# simple-loop2.net
KiCad netlist of a schematic drawn in EAGLE
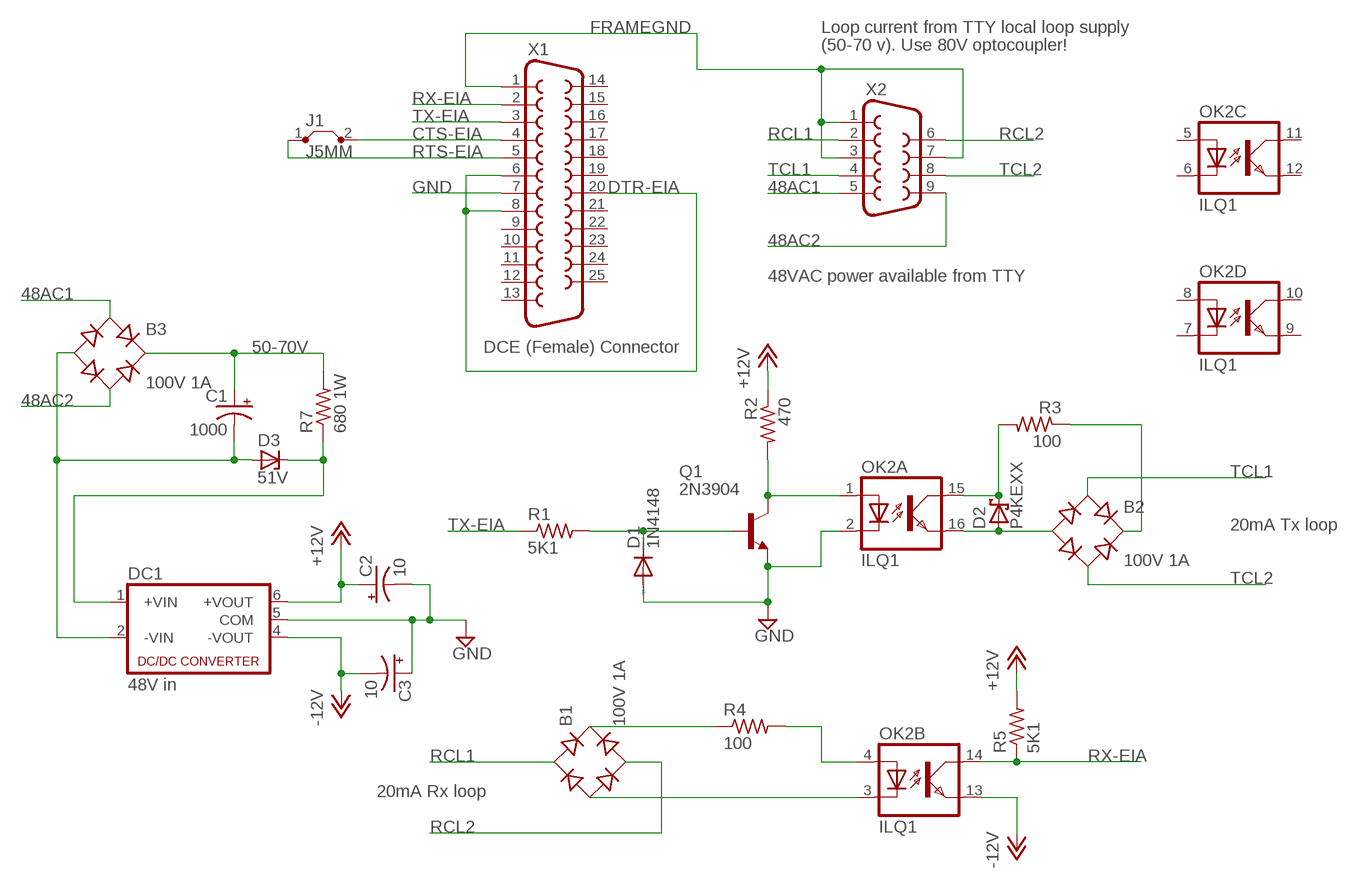
[diagram p0: schematic, sheet 1]

(export (version "E")
  (design (tool "Eeschema 10.0.6"))
  (components
    (comp (ref "B1")
      (value "100V 1A")
      (footprint "eagle-import:RB1A")
      (libsource (lib "eagle-import") (part "RB1A"))
    )
    (comp (ref "B2")
      (value "100V 1A")
      (footprint "eagle-import:RB1A")
      (libsource (lib "eagle-import") (part "RB1A"))
    )
    (comp (ref "B3")
      (value "100V 1A")
      (footprint "eagle-import:RB1A")
      (libsource (lib "eagle-import") (part "RB1A"))
    )
    (comp (ref "C1")
      (value "1000")
      (footprint "eagle-import:E7,5-18")
      (libsource (lib "eagle-import") (part "CPOL-USE7.5-18"))
    )
    (comp (ref "C2")
      (value "10")
      (footprint "eagle-import:B45181A")
      (libsource (lib "eagle-import") (part "CPOL-USB45181A"))
    )
    (comp (ref "C3")
      (value "10")
      (footprint "eagle-import:B45181A")
      (libsource (lib "eagle-import") (part "CPOL-USB45181A"))
    )
    (comp (ref "D1")
      (value "1N4148")
      (footprint "eagle-import:DO35-10")
      (libsource (lib "eagle-import") (part "1N4148DO35-10"))
    )
    (comp (ref "D2")
      (value "P4KEXX")
      (footprint "eagle-import:DO41-10")
      (libsource (lib "eagle-import") (part "P4KEXX"))
    )
    (comp (ref "D3")
      (value "51V")
      (footprint "eagle-import:DO41Z10")
      (libsource (lib "eagle-import") (part "ZENER-DIODEDO41Z10"))
    )
    (comp (ref "DC1")
      (value "48V in")
      (footprint "eagle-import:NMA")
      (fields (field (name "MF") "C & D TECHNOLOGIES, INC") (field (name "MPN") "NMA0515SC"))
      (libsource (lib "eagle-import") (part "NMA"))
    )
    (comp (ref "J1")
      (value "J5MM")
      (footprint "eagle-import:05")
      (libsource (lib "eagle-import") (part "J5MM"))
    )
    (comp (ref "OK2")
      (value "ILQ1")
      (footprint "eagle-import:DIL16")
      (fields (field (name "MF") "VISHAY/TELEFUNKEN"))
      (libsource (lib "eagle-import") (part "ILQ1"))
    )
    (comp (ref "Q1")
      (value "2N3904")
      (footprint "eagle-import:TO92")
      (libsource (lib "eagle-import") (part "2N3904"))
    )
    (comp (ref "R1")
      (value "5K1")
      (footprint "eagle-import:0207_10")
      (libsource (lib "eagle-import") (part "R-US_0207/10"))
    )
    (comp (ref "R2")
      (value "470")
      (footprint "eagle-import:0207_10")
      (libsource (lib "eagle-import") (part "R-US_0207/10"))
    )
    (comp (ref "R3")
      (value "100")
      (footprint "eagle-import:0207_10")
      (libsource (lib "eagle-import") (part "R-US_0207/10"))
    )
    (comp (ref "R4")
      (value "100")
      (footprint "eagle-import:0207_10")
      (libsource (lib "eagle-import") (part "R-US_0207/10"))
    )
    (comp (ref "R5")
      (value "5K1")
      (footprint "eagle-import:0207_10")
      (libsource (lib "eagle-import") (part "R-US_0207/10"))
    )
    (comp (ref "R7")
      (value "680 1W")
      (footprint "eagle-import:0617_17")
      (libsource (lib "eagle-import") (part "R-US_0617/17"))
    )
    (comp (ref "X1")
      (value "F25H")
      (footprint "eagle-import:F25H")
      (libsource (lib "eagle-import") (part "F25H"))
    )
    (comp (ref "X2")
      (value "F09H")
      (footprint "eagle-import:F09H")
      (libsource (lib "eagle-import") (part "F09H"))
    )
  )
  (nets
    (net (code "1") (name "+12V") (class "Default")
      (node (ref "C2") (pin "+") (pinfunction "+_+") (pintype "passive"))
      (node (ref "DC1") (pin "6") (pinfunction "+VOUT_6") (pintype "passive"))
      (node (ref "R2") (pin "1") (pinfunction "1_1") (pintype "passive"))
      (node (ref "R5") (pin "2") (pinfunction "2_2") (pintype "passive"))
    )
    (net (code "2") (name "-12V") (class "Default")
      (node (ref "C3") (pin "-") (pinfunction "-_-") (pintype "passive"))
      (node (ref "DC1") (pin "4") (pinfunction "-VOUT_4") (pintype "passive"))
      (node (ref "OK2") (pin "13") (pinfunction "EMIT_13") (pintype "passive"))
    )
    (net (code "3") (name "/48AC1") (class "Default")
      (node (ref "B3") (pin "AC1") (pinfunction "AC1_AC1") (pintype "passive"))
      (node (ref "X2") (pin "5") (pinfunction "5_5") (pintype "passive"))
    )
    (net (code "4") (name "/48AC2") (class "Default")
      (node (ref "B3") (pin "AC2") (pinfunction "AC2_AC2") (pintype "passive"))
      (node (ref "X2") (pin "9") (pinfunction "9_9") (pintype "passive"))
    )
    (net (code "5") (name "/50-70V") (class "Default")
      (node (ref "B3") (pin "+") (pinfunction "+_+") (pintype "passive"))
      (node (ref "C1") (pin "+") (pinfunction "+_+") (pintype "passive"))
      (node (ref "R7") (pin "2") (pinfunction "2_2") (pintype "passive"))
    )
    (net (code "6") (name "/CTS-EIA") (class "Default")
      (node (ref "J1") (pin "2") (pinfunction "2_2") (pintype "passive"))
      (node (ref "X1") (pin "4") (pinfunction "4_4") (pintype "passive"))
    )
    (net (code "7") (name "/DTR-EIA") (class "Default")
      (node (ref "X1") (pin "20") (pinfunction "20_20") (pintype "passive"))
      (node (ref "X1") (pin "6") (pinfunction "6_6") (pintype "passive"))
      (node (ref "X1") (pin "8") (pinfunction "8_8") (pintype "passive"))
    )
    (net (code "8") (name "/FRAMEGND") (class "Default")
      (node (ref "X1") (pin "1") (pinfunction "1_1") (pintype "passive"))
      (node (ref "X2") (pin "1") (pinfunction "1_1") (pintype "passive"))
      (node (ref "X2") (pin "3") (pinfunction "3_3") (pintype "passive"))
      (node (ref "X2") (pin "7") (pinfunction "7_7") (pintype "passive"))
    )
    (net (code "9") (name "/RCL1") (class "Default")
      (node (ref "B1") (pin "AC1") (pinfunction "AC1_AC1") (pintype "passive"))
      (node (ref "X2") (pin "2") (pinfunction "2_2") (pintype "passive"))
    )
    (net (code "10") (name "/RCL2") (class "Default")
      (node (ref "B1") (pin "AC2") (pinfunction "AC2_AC2") (pintype "passive"))
      (node (ref "X2") (pin "6") (pinfunction "6_6") (pintype "passive"))
    )
    (net (code "11") (name "/RTS-EIA") (class "Default")
      (node (ref "J1") (pin "1") (pinfunction "1_1") (pintype "passive"))
      (node (ref "X1") (pin "5") (pinfunction "5_5") (pintype "passive"))
    )
    (net (code "12") (name "/RX-EIA") (class "Default")
      (node (ref "OK2") (pin "14") (pinfunction "COL_14") (pintype "passive"))
      (node (ref "R5") (pin "1") (pinfunction "1_1") (pintype "passive"))
      (node (ref "X1") (pin "2") (pinfunction "2_2") (pintype "passive"))
    )
    (net (code "13") (name "/TCL1") (class "Default")
      (node (ref "B2") (pin "AC1") (pinfunction "AC1_AC1") (pintype "passive"))
      (node (ref "X2") (pin "4") (pinfunction "4_4") (pintype "passive"))
    )
    (net (code "14") (name "/TCL2") (class "Default")
      (node (ref "B2") (pin "AC2") (pinfunction "AC2_AC2") (pintype "passive"))
      (node (ref "X2") (pin "8") (pinfunction "8_8") (pintype "passive"))
    )
    (net (code "15") (name "/TX-EIA") (class "Default")
      (node (ref "R1") (pin "1") (pinfunction "1_1") (pintype "passive"))
      (node (ref "X1") (pin "3") (pinfunction "3_3") (pintype "passive"))
    )
    (net (code "16") (name "GND") (class "Default")
      (node (ref "C2") (pin "-") (pinfunction "-_-") (pintype "passive"))
      (node (ref "C3") (pin "+") (pinfunction "+_+") (pintype "passive"))
      (node (ref "D1") (pin "A") (pinfunction "A_A") (pintype "passive"))
      (node (ref "DC1") (pin "5") (pinfunction "COM_5") (pintype "passive"))
      (node (ref "OK2") (pin "2") (pinfunction "C_2") (pintype "passive"))
      (node (ref "Q1") (pin "3") (pinfunction "E_3") (pintype "passive"))
      (node (ref "X1") (pin "7") (pinfunction "7_7") (pintype "passive"))
    )
    (net (code "17") (name "Net-(B1-Pad+)") (class "Default")
      (node (ref "B1") (pin "+") (pinfunction "+_+") (pintype "passive"))
      (node (ref "R4") (pin "1") (pinfunction "1_1") (pintype "passive"))
    )
    (net (code "18") (name "Net-(B2-Pad+)") (class "Default")
      (node (ref "B2") (pin "+") (pinfunction "+_+") (pintype "passive"))
      (node (ref "R3") (pin "1") (pinfunction "1_1") (pintype "passive"))
    )
    (net (code "19") (name "Net-(DC1-+VIN)") (class "Default")
      (node (ref "D3") (pin "C") (pinfunction "C_C") (pintype "passive"))
      (node (ref "DC1") (pin "1") (pinfunction "+VIN_1") (pintype "passive"))
      (node (ref "R7") (pin "1") (pinfunction "1_1") (pintype "passive"))
    )
    (net (code "20") (name "Net-(DC1--VIN)") (class "Default")
      (node (ref "B3") (pin "-") (pinfunction "-_-") (pintype "passive"))
      (node (ref "C1") (pin "-") (pinfunction "-_-") (pintype "passive"))
      (node (ref "D3") (pin "A") (pinfunction "A_A") (pintype "passive"))
      (node (ref "DC1") (pin "2") (pinfunction "-VIN_2") (pintype "passive"))
    )
    (net (code "21") (name "Net-(OK2A-A)") (class "Default")
      (node (ref "OK2") (pin "1") (pinfunction "A_1") (pintype "passive"))
      (node (ref "Q1") (pin "1") (pinfunction "C_1") (pintype "passive"))
      (node (ref "R2") (pin "2") (pinfunction "2_2") (pintype "passive"))
    )
    (net (code "22") (name "Net-(OK2A-COL)") (class "Default")
      (node (ref "D2") (pin "C") (pinfunction "C_C") (pintype "passive"))
      (node (ref "OK2") (pin "15") (pinfunction "COL_15") (pintype "passive"))
      (node (ref "R3") (pin "2") (pinfunction "2_2") (pintype "passive"))
    )
    (net (code "23") (name "Net-(OK2A-EMIT)") (class "Default")
      (node (ref "B2") (pin "-") (pinfunction "-_-") (pintype "passive"))
      (node (ref "D2") (pin "A") (pinfunction "A_A") (pintype "passive"))
      (node (ref "OK2") (pin "16") (pinfunction "EMIT_16") (pintype "passive"))
    )
    (net (code "24") (name "Net-(OK2B-A)") (class "Default")
      (node (ref "OK2") (pin "4") (pinfunction "A_4") (pintype "passive"))
      (node (ref "R4") (pin "2") (pinfunction "2_2") (pintype "passive"))
    )
    (net (code "25") (name "Net-(OK2B-C)") (class "Default")
      (node (ref "B1") (pin "-") (pinfunction "-_-") (pintype "passive"))
      (node (ref "OK2") (pin "3") (pinfunction "C_3") (pintype "passive"))
    )
    (net (code "26") (name "Net-(Q1-B)") (class "Default")
      (node (ref "D1") (pin "C") (pinfunction "C_C") (pintype "passive"))
      (node (ref "Q1") (pin "2") (pinfunction "B_2") (pintype "passive"))
      (node (ref "R1") (pin "2") (pinfunction "2_2") (pintype "passive"))
    )
    (net (code "27") (name "unconnected-(OK2C-A-Pad5)") (class "Default")
      (node (ref "OK2") (pin "5") (pinfunction "A_5") (pintype "passive"))
    )
    (net (code "28") (name "unconnected-(OK2C-C-Pad6)") (class "Default")
      (node (ref "OK2") (pin "6") (pinfunction "C_6") (pintype "passive"))
    )
    (net (code "29") (name "unconnected-(OK2C-COL-Pad11)") (class "Default")
      (node (ref "OK2") (pin "11") (pinfunction "COL_11") (pintype "passive"))
    )
    (net (code "30") (name "unconnected-(OK2C-EMIT-Pad12)") (class "Default")
      (node (ref "OK2") (pin "12") (pinfunction "EMIT_12") (pintype "passive"))
    )
    (net (code "31") (name "unconnected-(OK2D-A-Pad8)") (class "Default")
      (node (ref "OK2") (pin "8") (pinfunction "A_8") (pintype "passive"))
    )
    (net (code "32") (name "unconnected-(OK2D-C-Pad7)") (class "Default")
      (node (ref "OK2") (pin "7") (pinfunction "C_7") (pintype "passive"))
    )
    (net (code "33") (name "unconnected-(OK2D-COL-Pad10)") (class "Default")
      (node (ref "OK2") (pin "10") (pinfunction "COL_10") (pintype "passive"))
    )
    (net (code "34") (name "unconnected-(OK2D-EMIT-Pad9)") (class "Default")
      (node (ref "OK2") (pin "9") (pinfunction "EMIT_9") (pintype "passive"))
    )
    (net (code "35") (name "unconnected-(X1-Pad9)") (class "Default")
      (node (ref "X1") (pin "9") (pinfunction "9_9") (pintype "passive"))
    )
    (net (code "36") (name "unconnected-(X1-Pad10)") (class "Default")
      (node (ref "X1") (pin "10") (pinfunction "10_10") (pintype "passive"))
    )
    (net (code "37") (name "unconnected-(X1-Pad11)") (class "Default")
      (node (ref "X1") (pin "11") (pinfunction "11_11") (pintype "passive"))
    )
    (net (code "38") (name "unconnected-(X1-Pad12)") (class "Default")
      (node (ref "X1") (pin "12") (pinfunction "12_12") (pintype "passive"))
    )
    (net (code "39") (name "unconnected-(X1-Pad13)") (class "Default")
      (node (ref "X1") (pin "13") (pinfunction "13_13") (pintype "passive"))
    )
    (net (code "40") (name "unconnected-(X1-Pad14)") (class "Default")
      (node (ref "X1") (pin "14") (pinfunction "14_14") (pintype "passive"))
    )
    (net (code "41") (name "unconnected-(X1-Pad15)") (class "Default")
      (node (ref "X1") (pin "15") (pinfunction "15_15") (pintype "passive"))
    )
    (net (code "42") (name "unconnected-(X1-Pad16)") (class "Default")
      (node (ref "X1") (pin "16") (pinfunction "16_16") (pintype "passive"))
    )
    (net (code "43") (name "unconnected-(X1-Pad17)") (class "Default")
      (node (ref "X1") (pin "17") (pinfunction "17_17") (pintype "passive"))
    )
    (net (code "44") (name "unconnected-(X1-Pad18)") (class "Default")
      (node (ref "X1") (pin "18") (pinfunction "18_18") (pintype "passive"))
    )
    (net (code "45") (name "unconnected-(X1-Pad19)") (class "Default")
      (node (ref "X1") (pin "19") (pinfunction "19_19") (pintype "passive"))
    )
    (net (code "46") (name "unconnected-(X1-Pad21)") (class "Default")
      (node (ref "X1") (pin "21") (pinfunction "21_21") (pintype "passive"))
    )
    (net (code "47") (name "unconnected-(X1-Pad22)") (class "Default")
      (node (ref "X1") (pin "22") (pinfunction "22_22") (pintype "passive"))
    )
    (net (code "48") (name "unconnected-(X1-Pad23)") (class "Default")
      (node (ref "X1") (pin "23") (pinfunction "23_23") (pintype "passive"))
    )
    (net (code "49") (name "unconnected-(X1-Pad24)") (class "Default")
      (node (ref "X1") (pin "24") (pinfunction "24_24") (pintype "passive"))
    )
    (net (code "50") (name "unconnected-(X1-Pad25)") (class "Default")
      (node (ref "X1") (pin "25") (pinfunction "25_25") (pintype "passive"))
    )
  )
)
